# ADPD103-Breakout.net
KiCad netlist of a schematic drawn in EAGLE
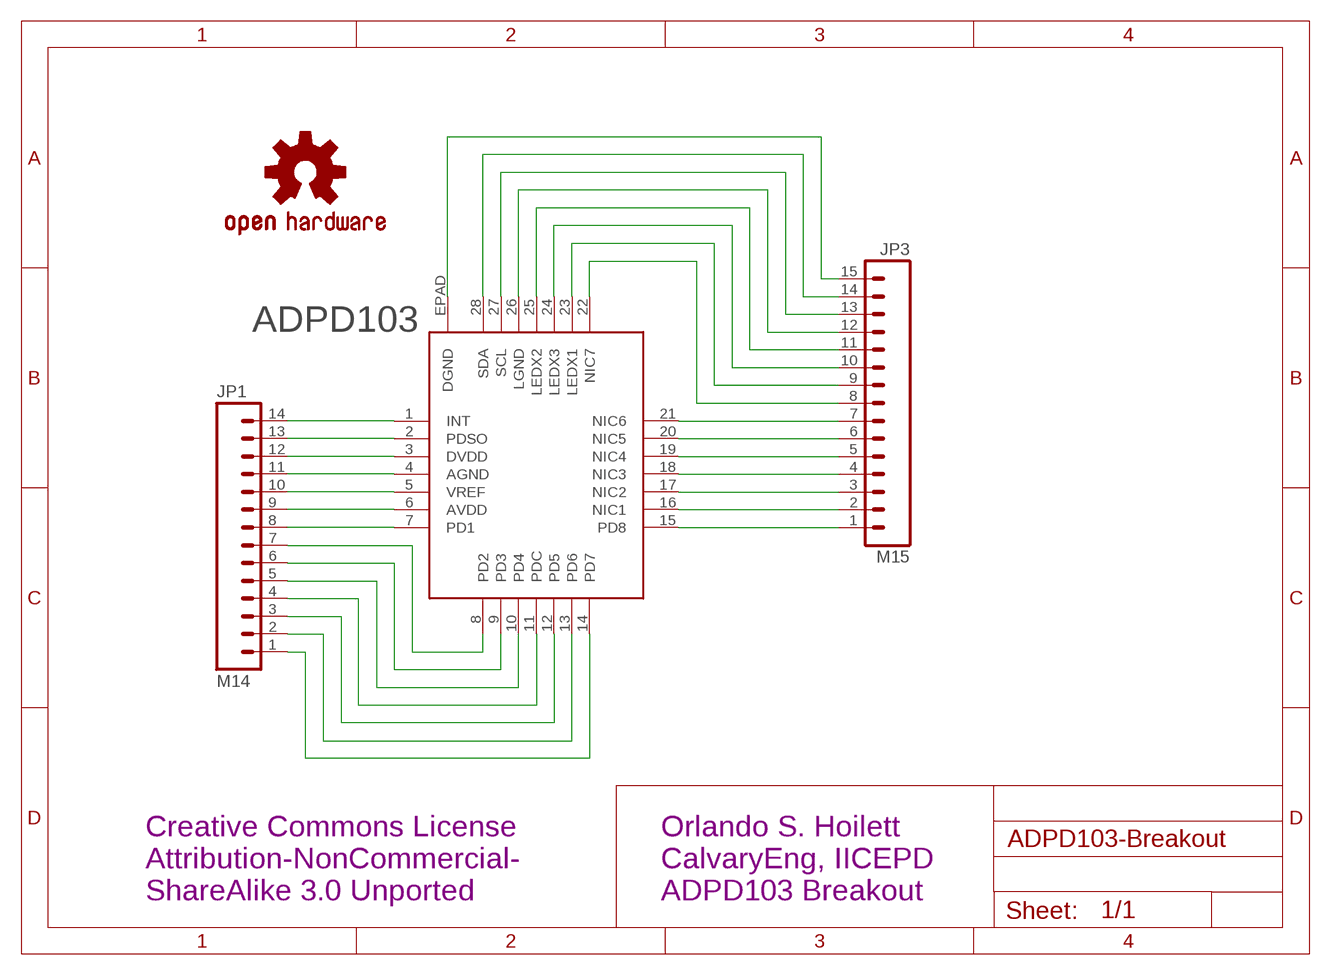
[diagram p0: schematic, sheet 1]

(export (version "E")
  (design (tool "Eeschema 10.0.6"))
  (components
    (comp (ref "JP1")
      (value "M14")
      (footprint "eagle-import:1X14")
      (libsource (lib "eagle-import") (part "M14"))
    )
    (comp (ref "JP3")
      (value "M15")
      (footprint "eagle-import:1X15")
      (libsource (lib "eagle-import") (part "M15"))
    )
    (comp (ref "LOGO1")
      (value "OSHW-LOGOS")
      (footprint "eagle-import:OSHW-LOGO-S")
      (libsource (lib "eagle-import") (part "OSHW-LOGOS"))
    )
    (comp (ref "U$1")
      (value "ADPD103")
      (footprint "eagle-import:28-LFCSP")
      (libsource (lib "eagle-import") (part "ADPD103"))
    )
  )
  (nets
    (net (code "1") (name "Net-(U$1-AGND)") (class "Default")
      (node (ref "JP1") (pin "11") (pinfunction "11_11") (pintype "passive"))
      (node (ref "U$1") (pin "4") (pinfunction "AGND_4") (pintype "bidirectional"))
    )
    (net (code "2") (name "Net-(U$1-AVDD)") (class "Default")
      (node (ref "JP1") (pin "9") (pinfunction "9_9") (pintype "passive"))
      (node (ref "U$1") (pin "6") (pinfunction "AVDD_6") (pintype "bidirectional"))
    )
    (net (code "3") (name "Net-(U$1-DGND)") (class "Default")
      (node (ref "JP3") (pin "15") (pinfunction "15_15") (pintype "passive"))
      (node (ref "U$1") (pin "EPAD") (pinfunction "DGND_EPAD") (pintype "bidirectional"))
    )
    (net (code "4") (name "Net-(U$1-DVDD)") (class "Default")
      (node (ref "JP1") (pin "12") (pinfunction "12_12") (pintype "passive"))
      (node (ref "U$1") (pin "3") (pinfunction "DVDD_3") (pintype "bidirectional"))
    )
    (net (code "5") (name "Net-(U$1-INT)") (class "Default")
      (node (ref "JP1") (pin "14") (pinfunction "14_14") (pintype "passive"))
      (node (ref "U$1") (pin "1") (pinfunction "INT_1") (pintype "bidirectional"))
    )
    (net (code "6") (name "Net-(U$1-LEDX1)") (class "Default")
      (node (ref "JP3") (pin "9") (pinfunction "9_9") (pintype "passive"))
      (node (ref "U$1") (pin "23") (pinfunction "LEDX1_23") (pintype "bidirectional"))
    )
    (net (code "7") (name "Net-(U$1-LEDX2)") (class "Default")
      (node (ref "JP3") (pin "11") (pinfunction "11_11") (pintype "passive"))
      (node (ref "U$1") (pin "25") (pinfunction "LEDX2_25") (pintype "bidirectional"))
    )
    (net (code "8") (name "Net-(U$1-LEDX3)") (class "Default")
      (node (ref "JP3") (pin "10") (pinfunction "10_10") (pintype "passive"))
      (node (ref "U$1") (pin "24") (pinfunction "LEDX3_24") (pintype "bidirectional"))
    )
    (net (code "9") (name "Net-(U$1-LGND)") (class "Default")
      (node (ref "JP3") (pin "12") (pinfunction "12_12") (pintype "passive"))
      (node (ref "U$1") (pin "26") (pinfunction "LGND_26") (pintype "bidirectional"))
    )
    (net (code "10") (name "Net-(U$1-NIC1)") (class "Default")
      (node (ref "JP3") (pin "2") (pinfunction "2_2") (pintype "passive"))
      (node (ref "U$1") (pin "16") (pinfunction "NIC1_16") (pintype "bidirectional"))
    )
    (net (code "11") (name "Net-(U$1-NIC2)") (class "Default")
      (node (ref "JP3") (pin "3") (pinfunction "3_3") (pintype "passive"))
      (node (ref "U$1") (pin "17") (pinfunction "NIC2_17") (pintype "bidirectional"))
    )
    (net (code "12") (name "Net-(U$1-NIC3)") (class "Default")
      (node (ref "JP3") (pin "4") (pinfunction "4_4") (pintype "passive"))
      (node (ref "U$1") (pin "18") (pinfunction "NIC3_18") (pintype "bidirectional"))
    )
    (net (code "13") (name "Net-(U$1-NIC4)") (class "Default")
      (node (ref "JP3") (pin "5") (pinfunction "5_5") (pintype "passive"))
      (node (ref "U$1") (pin "19") (pinfunction "NIC4_19") (pintype "bidirectional"))
    )
    (net (code "14") (name "Net-(U$1-NIC5)") (class "Default")
      (node (ref "JP3") (pin "6") (pinfunction "6_6") (pintype "passive"))
      (node (ref "U$1") (pin "20") (pinfunction "NIC5_20") (pintype "bidirectional"))
    )
    (net (code "15") (name "Net-(U$1-NIC6)") (class "Default")
      (node (ref "JP3") (pin "7") (pinfunction "7_7") (pintype "passive"))
      (node (ref "U$1") (pin "21") (pinfunction "NIC6_21") (pintype "bidirectional"))
    )
    (net (code "16") (name "Net-(U$1-NIC7)") (class "Default")
      (node (ref "JP3") (pin "8") (pinfunction "8_8") (pintype "passive"))
      (node (ref "U$1") (pin "22") (pinfunction "NIC7_22") (pintype "bidirectional"))
    )
    (net (code "17") (name "Net-(U$1-PD1)") (class "Default")
      (node (ref "JP1") (pin "8") (pinfunction "8_8") (pintype "passive"))
      (node (ref "U$1") (pin "7") (pinfunction "PD1_7") (pintype "bidirectional"))
    )
    (net (code "18") (name "Net-(U$1-PD2)") (class "Default")
      (node (ref "JP1") (pin "7") (pinfunction "7_7") (pintype "passive"))
      (node (ref "U$1") (pin "8") (pinfunction "PD2_8") (pintype "bidirectional"))
    )
    (net (code "19") (name "Net-(U$1-PD3)") (class "Default")
      (node (ref "JP1") (pin "6") (pinfunction "6_6") (pintype "passive"))
      (node (ref "U$1") (pin "9") (pinfunction "PD3_9") (pintype "bidirectional"))
    )
    (net (code "20") (name "Net-(U$1-PD4)") (class "Default")
      (node (ref "JP1") (pin "5") (pinfunction "5_5") (pintype "passive"))
      (node (ref "U$1") (pin "10") (pinfunction "PD4_10") (pintype "bidirectional"))
    )
    (net (code "21") (name "Net-(U$1-PD5)") (class "Default")
      (node (ref "JP1") (pin "3") (pinfunction "3_3") (pintype "passive"))
      (node (ref "U$1") (pin "12") (pinfunction "PD5_12") (pintype "bidirectional"))
    )
    (net (code "22") (name "Net-(U$1-PD6)") (class "Default")
      (node (ref "JP1") (pin "2") (pinfunction "2_2") (pintype "passive"))
      (node (ref "U$1") (pin "13") (pinfunction "PD6_13") (pintype "bidirectional"))
    )
    (net (code "23") (name "Net-(U$1-PD7)") (class "Default")
      (node (ref "JP1") (pin "1") (pinfunction "1_1") (pintype "passive"))
      (node (ref "U$1") (pin "14") (pinfunction "PD7_14") (pintype "bidirectional"))
    )
    (net (code "24") (name "Net-(U$1-PD8)") (class "Default")
      (node (ref "JP3") (pin "1") (pinfunction "1_1") (pintype "passive"))
      (node (ref "U$1") (pin "15") (pinfunction "PD8_15") (pintype "bidirectional"))
    )
    (net (code "25") (name "Net-(U$1-PDC)") (class "Default")
      (node (ref "JP1") (pin "4") (pinfunction "4_4") (pintype "passive"))
      (node (ref "U$1") (pin "11") (pinfunction "PDC_11") (pintype "bidirectional"))
    )
    (net (code "26") (name "Net-(U$1-PDSO)") (class "Default")
      (node (ref "JP1") (pin "13") (pinfunction "13_13") (pintype "passive"))
      (node (ref "U$1") (pin "2") (pinfunction "PDSO_2") (pintype "bidirectional"))
    )
    (net (code "27") (name "Net-(U$1-SCL)") (class "Default")
      (node (ref "JP3") (pin "13") (pinfunction "13_13") (pintype "passive"))
      (node (ref "U$1") (pin "27") (pinfunction "SCL_27") (pintype "bidirectional"))
    )
    (net (code "28") (name "Net-(U$1-SDA)") (class "Default")
      (node (ref "JP3") (pin "14") (pinfunction "14_14") (pintype "passive"))
      (node (ref "U$1") (pin "28") (pinfunction "SDA_28") (pintype "bidirectional"))
    )
    (net (code "29") (name "Net-(U$1-VREF)") (class "Default")
      (node (ref "JP1") (pin "10") (pinfunction "10_10") (pintype "passive"))
      (node (ref "U$1") (pin "5") (pinfunction "VREF_5") (pintype "bidirectional"))
    )
  )
)
